# Comp_Clipper.net
KiCad netlist of a schematic drawn in Altium Designer
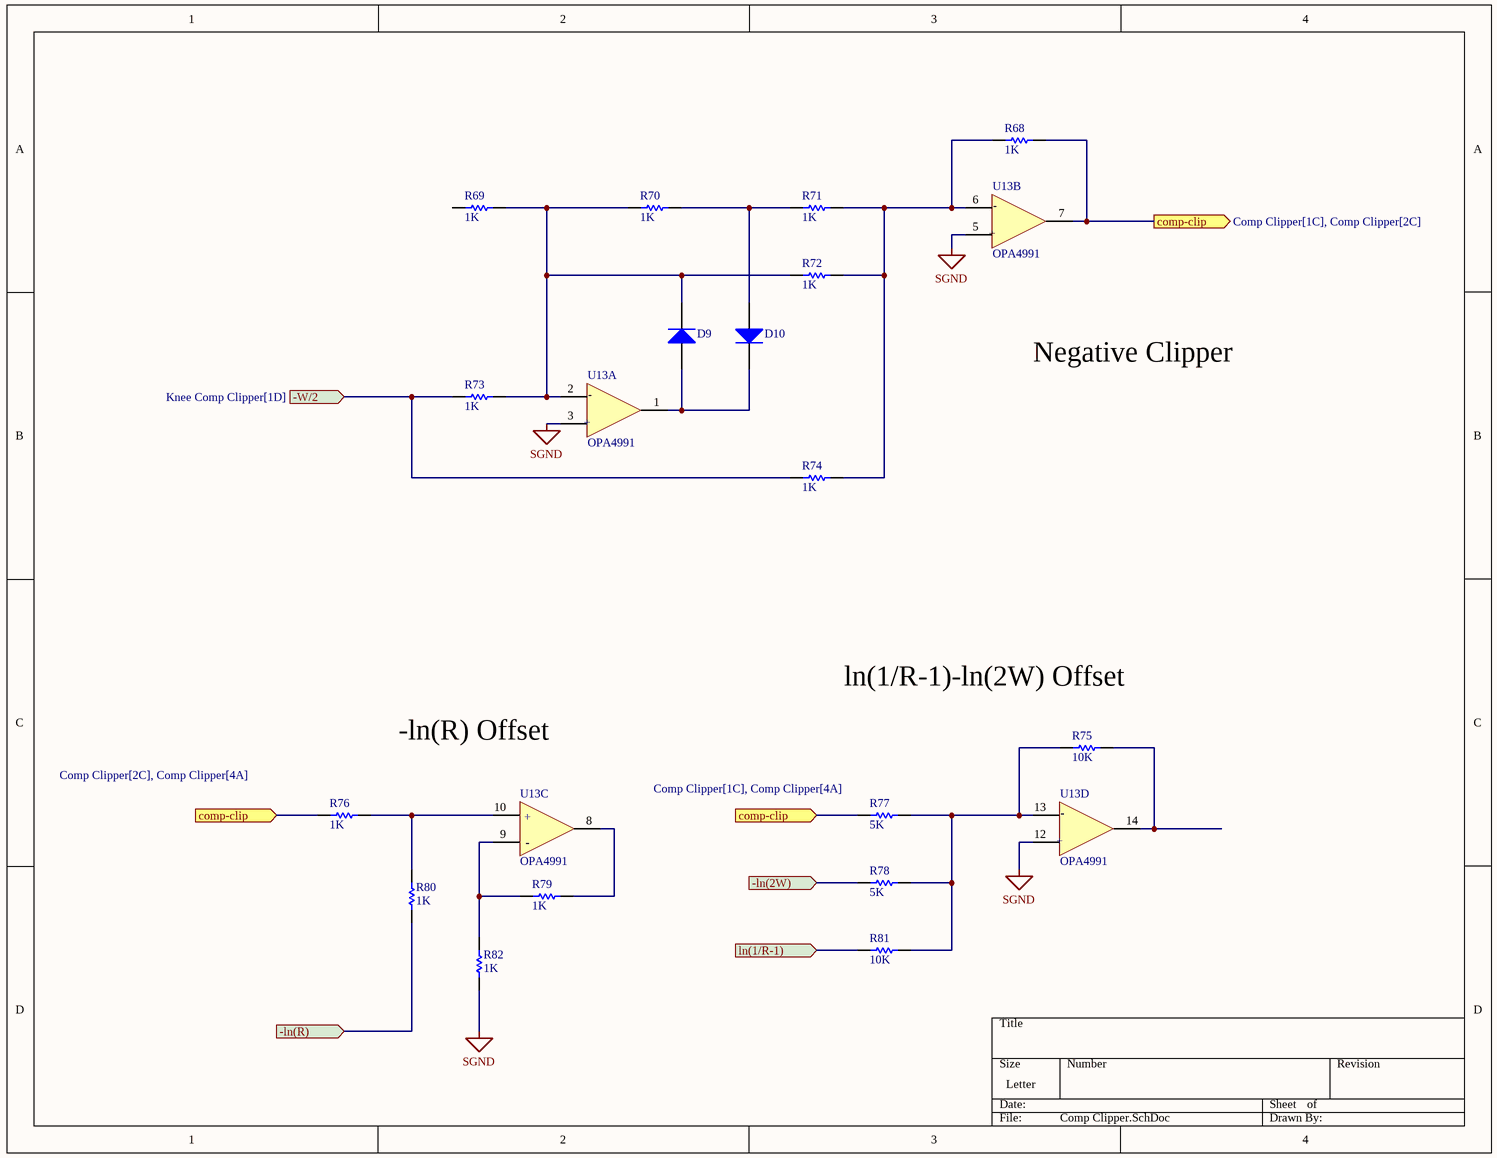
[diagram p0: Comp Clipper.SchDoc]

(export (version "E")
  (design (tool "Eeschema 10.0.6"))
  (components
    (comp (ref "D9") (value "Diode") (libsource (lib "Simulation Generic Components") (part "Diode")))
    (comp (ref "D10") (value "Diode") (libsource (lib "Simulation Generic Components") (part "Diode")))
    (comp (ref "R68")
      (value "1K")
      (description "Resistor")
      (libsource (lib "Simulation Generic Components") (part "Resistor"))
    )
    (comp (ref "R69")
      (value "1K")
      (description "Resistor")
      (libsource (lib "Simulation Generic Components") (part "Resistor"))
    )
    (comp (ref "R70")
      (value "1K")
      (description "Resistor")
      (libsource (lib "Simulation Generic Components") (part "Resistor"))
    )
    (comp (ref "R71")
      (value "1K")
      (description "Resistor")
      (libsource (lib "Simulation Generic Components") (part "Resistor"))
    )
    (comp (ref "R72")
      (value "1K")
      (description "Resistor")
      (libsource (lib "Simulation Generic Components") (part "Resistor"))
    )
    (comp (ref "R73")
      (value "1K")
      (description "Resistor")
      (libsource (lib "Simulation Generic Components") (part "Resistor"))
    )
    (comp (ref "R74")
      (value "1K")
      (description "Resistor")
      (libsource (lib "Simulation Generic Components") (part "Resistor"))
    )
    (comp (ref "R75")
      (value "10K")
      (description "Resistor")
      (libsource (lib "Simulation Generic Components") (part "Resistor"))
    )
    (comp (ref "R76")
      (value "1K")
      (description "Resistor")
      (libsource (lib "Simulation Generic Components") (part "Resistor"))
    )
    (comp (ref "R77")
      (value "5K")
      (description "Resistor")
      (libsource (lib "Simulation Generic Components") (part "Resistor"))
    )
    (comp (ref "R78")
      (value "5K")
      (description "Resistor")
      (libsource (lib "Simulation Generic Components") (part "Resistor"))
    )
    (comp (ref "R79")
      (value "1K")
      (description "Resistor")
      (libsource (lib "Simulation Generic Components") (part "Resistor"))
    )
    (comp (ref "R80")
      (value "1K")
      (description "Resistor")
      (libsource (lib "Simulation Generic Components") (part "Resistor"))
    )
    (comp (ref "R81")
      (value "10K")
      (description "Resistor")
      (libsource (lib "Simulation Generic Components") (part "Resistor"))
    )
    (comp (ref "R82")
      (value "1K")
      (description "Resistor")
      (libsource (lib "Simulation Generic Components") (part "Resistor"))
    )
    (comp (ref "U13")
      (value "OPA4991")
      (footprint "FP-D0014A-IPC_B")
      (description "40-V, DUAL 4.5MHZ, RAIL-TO-RAIL")
      (libsource (lib "DRC") (part "OPA4991IDR"))
    )
  )
  (nets
    (net (code "1") (name "/-W{slash}2") (class "Default")
      (node (ref "R73") (pin "1") (pinfunction "1_1") (pintype "passive"))
      (node (ref "R74") (pin "1") (pinfunction "1_1") (pintype "passive"))
    )
    (net (code "2") (name "/-ln(2W)") (class "Default")
      (node (ref "R78") (pin "2") (pinfunction "2_2") (pintype "passive"))
    )
    (net (code "3") (name "/-ln(R)") (class "Default")
      (node (ref "R80") (pin "1") (pinfunction "1_1") (pintype "passive"))
    )
    (net (code "4") (name "/comp-clip") (class "Default")
      (node (ref "R68") (pin "2") (pinfunction "2_2") (pintype "passive"))
      (node (ref "R76") (pin "1") (pinfunction "1_1") (pintype "passive"))
      (node (ref "R77") (pin "1") (pinfunction "1_1") (pintype "passive"))
      (node (ref "U13") (pin "7") (pinfunction "OUT2_7") (pintype "passive"))
    )
    (net (code "5") (name "/ln(1{slash}R-1)") (class "Default")
      (node (ref "R81") (pin "1") (pinfunction "1_1") (pintype "passive"))
    )
    (net (code "6") (name "Net-(D9-K)") (class "Default")
      (node (ref "D9") (pin "2") (pinfunction "K_2") (pintype "passive"))
      (node (ref "R69") (pin "2") (pinfunction "2_2") (pintype "passive"))
      (node (ref "R70") (pin "1") (pinfunction "1_1") (pintype "passive"))
      (node (ref "R72") (pin "1") (pinfunction "1_1") (pintype "passive"))
      (node (ref "R73") (pin "2") (pinfunction "2_2") (pintype "passive"))
      (node (ref "U13") (pin "2") (pinfunction "IN1-_2") (pintype "tri_state"))
    )
    (net (code "7") (name "Net-(D10-A)") (class "Default")
      (node (ref "D10") (pin "1") (pinfunction "A_1") (pintype "passive"))
      (node (ref "R70") (pin "2") (pinfunction "2_2") (pintype "passive"))
      (node (ref "R71") (pin "1") (pinfunction "1_1") (pintype "passive"))
    )
    (net (code "8") (name "Net-(D10-K)") (class "Default")
      (node (ref "D10") (pin "2") (pinfunction "K_2") (pintype "passive"))
      (node (ref "D9") (pin "1") (pinfunction "A_1") (pintype "passive"))
      (node (ref "U13") (pin "1") (pinfunction "OUT1_1") (pintype "passive"))
    )
    (net (code "9") (name "Net-(U13B-IN2-)") (class "Default")
      (node (ref "R68") (pin "1") (pinfunction "1_1") (pintype "passive"))
      (node (ref "R71") (pin "2") (pinfunction "2_2") (pintype "passive"))
      (node (ref "R72") (pin "2") (pinfunction "2_2") (pintype "passive"))
      (node (ref "R74") (pin "2") (pinfunction "2_2") (pintype "passive"))
      (node (ref "U13") (pin "6") (pinfunction "IN2-_6") (pintype "tri_state"))
    )
    (net (code "10") (name "Net-(U13C-IN3+)") (class "Default")
      (node (ref "R76") (pin "2") (pinfunction "2_2") (pintype "passive"))
      (node (ref "R80") (pin "2") (pinfunction "2_2") (pintype "passive"))
      (node (ref "U13") (pin "10") (pinfunction "IN3+_10") (pintype "tri_state"))
    )
    (net (code "11") (name "Net-(U13C-IN3-)") (class "Default")
      (node (ref "R79") (pin "2") (pinfunction "2_2") (pintype "passive"))
      (node (ref "R82") (pin "1") (pinfunction "1_1") (pintype "passive"))
      (node (ref "U13") (pin "9") (pinfunction "IN3-_9") (pintype "tri_state"))
    )
    (net (code "12") (name "Net-(U13C-OUT3)") (class "Default")
      (node (ref "R79") (pin "1") (pinfunction "1_1") (pintype "passive"))
      (node (ref "U13") (pin "8") (pinfunction "OUT3_8") (pintype "passive"))
    )
    (net (code "13") (name "Net-(U13D-IN4-)") (class "Default")
      (node (ref "R75") (pin "2") (pinfunction "2_2") (pintype "passive"))
      (node (ref "R77") (pin "2") (pinfunction "2_2") (pintype "passive"))
      (node (ref "R78") (pin "1") (pinfunction "1_1") (pintype "passive"))
      (node (ref "R81") (pin "2") (pinfunction "2_2") (pintype "passive"))
      (node (ref "U13") (pin "13") (pinfunction "IN4-_13") (pintype "tri_state"))
    )
    (net (code "14") (name "Net-(U13D-OUT4)") (class "Default")
      (node (ref "R75") (pin "1") (pinfunction "1_1") (pintype "passive"))
      (node (ref "U13") (pin "14") (pinfunction "OUT4_14") (pintype "passive"))
    )
    (net (code "15") (name "SGND") (class "Default")
      (node (ref "R82") (pin "2") (pinfunction "2_2") (pintype "passive"))
      (node (ref "U13") (pin "12") (pinfunction "IN4+_12") (pintype "tri_state"))
      (node (ref "U13") (pin "3") (pinfunction "IN1+_3") (pintype "tri_state"))
      (node (ref "U13") (pin "5") (pinfunction "IN2+_5") (pintype "tri_state"))
    )
    (net (code "16") (name "unconnected-(R69-Pad1)") (class "Default")
      (node (ref "R69") (pin "1") (pinfunction "1_1") (pintype "passive"))
    )
  )
)
